# DC4dazzer2.net
KiCad netlist of a schematic drawn in EAGLE
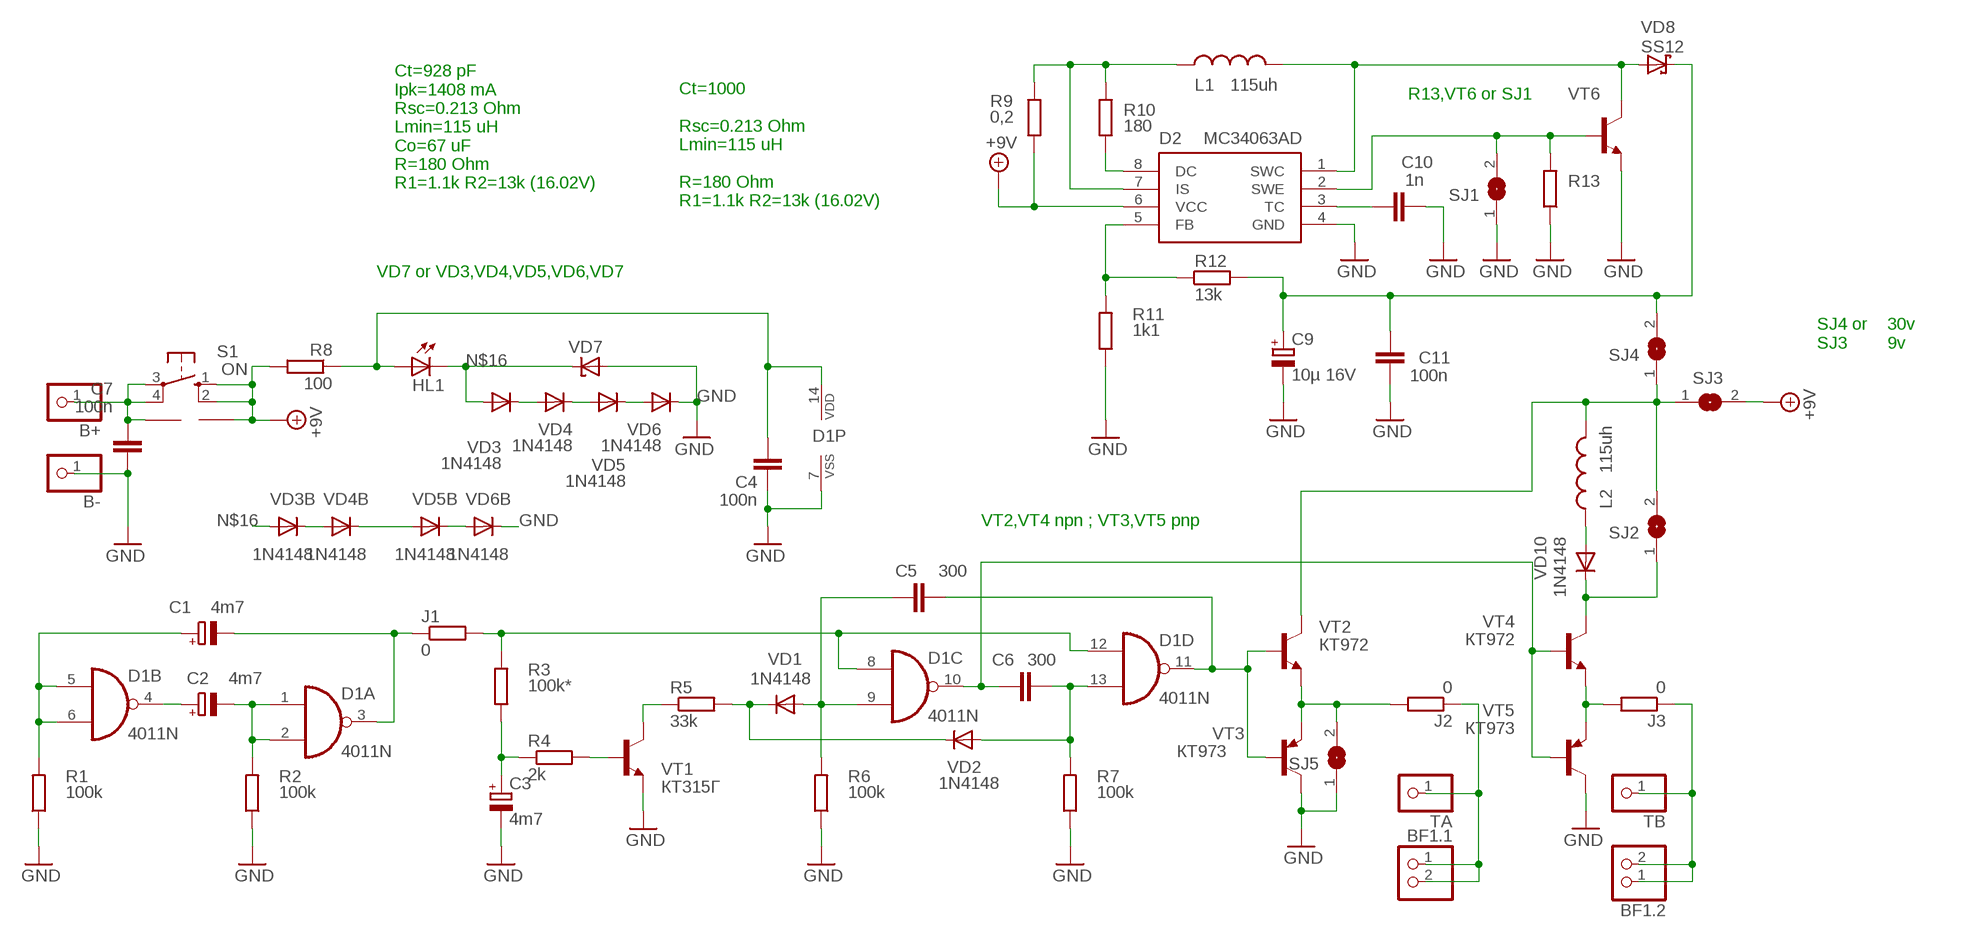
[diagram p0: schematic, sheet 1]

(export (version "E")
  (design (tool "Eeschema 10.0.6"))
  (components
    (comp (ref "B+")
      (value "PINHD-1X1")
      (footprint "eagle-import:1X01")
      (libsource (lib "eagle-import") (part "PINHD-1X1"))
    )
    (comp (ref "B-")
      (value "PINHD-1X1")
      (footprint "eagle-import:1X01")
      (libsource (lib "eagle-import") (part "PINHD-1X1"))
    )
    (comp (ref "BF1.1")
      (value "PINHD-1X2")
      (footprint "eagle-import:1X02")
      (libsource (lib "eagle-import") (part "PINHD-1X2"))
    )
    (comp (ref "BF1.2")
      (value "PINHD-1X2")
      (footprint "eagle-import:1X02")
      (libsource (lib "eagle-import") (part "PINHD-1X2"))
    )
    (comp (ref "C1")
      (value "4m7")
      (footprint "eagle-import:E3,5-8")
      (libsource (lib "eagle-import") (part "CPOL-EUE3.5-8"))
    )
    (comp (ref "C2")
      (value "4m7")
      (footprint "eagle-import:E2,5-7")
      (libsource (lib "eagle-import") (part "CPOL-EUE2.5-7"))
    )
    (comp (ref "C3")
      (value "4m7")
      (footprint "eagle-import:E2,5-7")
      (libsource (lib "eagle-import") (part "CPOL-EUE2.5-7"))
    )
    (comp (ref "C4")
      (value "100n")
      (footprint "eagle-import:C0805")
      (libsource (lib "eagle-import") (part "rcl_C-EUC0805"))
    )
    (comp (ref "C5")
      (value "300")
      (footprint "eagle-import:CAP-PTH-LARGE")
      (libsource (lib "eagle-import") (part "CAPPTH3"))
    )
    (comp (ref "C6")
      (value "300")
      (footprint "eagle-import:CAP-PTH-LARGE")
      (libsource (lib "eagle-import") (part "CAPPTH3"))
    )
    (comp (ref "C7")
      (value "100n")
      (footprint "eagle-import:C025-024X044")
      (libsource (lib "eagle-import") (part "C-EU025-024X044"))
    )
    (comp (ref "C9")
      (value "10µ 16V")
      (footprint "eagle-import:RCL_E3,5-8")
      (libsource (lib "eagle-import") (part "RCL_CPOL-EUE3.5-8"))
    )
    (comp (ref "C10")
      (value "1n")
      (footprint "eagle-import:C025-025X050")
      (libsource (lib "eagle-import") (part "rcl_C-EU025-025X050"))
    )
    (comp (ref "C11")
      (value "100n")
      (footprint "eagle-import:C0805")
      (libsource (lib "eagle-import") (part "rcl_C-EUC0805"))
    )
    (comp (ref "D1")
      (value "4011N")
      (footprint "eagle-import:DIL14")
      (libsource (lib "eagle-import") (part "4011N"))
    )
    (comp (ref "D2")
      (value "MC34063AD")
      (footprint "eagle-import:SOIC8")
      (libsource (lib "eagle-import") (part "MC34063AD"))
    )
    (comp (ref "HL1")
      (value "LED5MM")
      (footprint "eagle-import:LED5MM")
      (libsource (lib "eagle-import") (part "LED5MM"))
    )
    (comp (ref "J1")
      (value "0")
      (footprint "eagle-import:R1206W")
      (libsource (lib "eagle-import") (part "R-EU_R1206W"))
    )
    (comp (ref "J2")
      (value "0")
      (footprint "eagle-import:R1206W")
      (libsource (lib "eagle-import") (part "R-EU_R1206W"))
    )
    (comp (ref "J3")
      (value "0")
      (footprint "eagle-import:R1206W")
      (libsource (lib "eagle-import") (part "R-EU_R1206W"))
    )
    (comp (ref "L1")
      (value "115uh")
      (footprint "eagle-import:0207_10")
      (libsource (lib "eagle-import") (part "L-US0207/10"))
    )
    (comp (ref "L2")
      (value "115uh")
      (footprint "eagle-import:0204_5")
      (libsource (lib "eagle-import") (part "L-US0204/5"))
    )
    (comp (ref "R1")
      (value "100k")
      (footprint "eagle-import:R0805")
      (libsource (lib "eagle-import") (part "R-EU_R0805"))
    )
    (comp (ref "R2")
      (value "100k")
      (footprint "eagle-import:R0805")
      (libsource (lib "eagle-import") (part "R-EU_R0805"))
    )
    (comp (ref "R3")
      (value "100k*")
      (footprint "eagle-import:0204_7")
      (libsource (lib "eagle-import") (part "R-EU_0204/7"))
    )
    (comp (ref "R4")
      (value "2k")
      (footprint "eagle-import:R0805")
      (libsource (lib "eagle-import") (part "R-EU_R0805"))
    )
    (comp (ref "R5")
      (value "33k")
      (footprint "eagle-import:R1206W")
      (libsource (lib "eagle-import") (part "R-EU_R1206W"))
    )
    (comp (ref "R6")
      (value "100k")
      (footprint "eagle-import:R1206W")
      (libsource (lib "eagle-import") (part "R-EU_R1206W"))
    )
    (comp (ref "R7")
      (value "100k")
      (footprint "eagle-import:M0805")
      (libsource (lib "eagle-import") (part "R-EU_M0805"))
    )
    (comp (ref "R8")
      (value "100")
      (footprint "eagle-import:0204_5")
      (libsource (lib "eagle-import") (part "R-EU_0204/5"))
    )
    (comp (ref "R9")
      (value "0,2")
      (footprint "eagle-import:0204_7")
      (libsource (lib "eagle-import") (part "R-EU_0204/7"))
    )
    (comp (ref "R10")
      (value "180")
      (footprint "eagle-import:0204_7")
      (libsource (lib "eagle-import") (part "R-EU_0204/7"))
    )
    (comp (ref "R11")
      (value "1k1")
      (footprint "eagle-import:M0805")
      (libsource (lib "eagle-import") (part "R-EU_M0805"))
    )
    (comp (ref "R12")
      (value "13k")
      (footprint "eagle-import:M0805")
      (libsource (lib "eagle-import") (part "R-EU_M0805"))
    )
    (comp (ref "R13")
      (value "R-EU_0204/7")
      (footprint "eagle-import:0204_7")
      (libsource (lib "eagle-import") (part "R-EU_0204/7"))
    )
    (comp (ref "S1")
      (value "ON")
      (footprint "eagle-import:B3F-10XX")
      (fields (field (name "MPN") "B3F-1000"))
      (libsource (lib "eagle-import") (part "10-XX"))
    )
    (comp (ref "SJ1") (value "SJ") (footprint "eagle-import:SJ") (libsource (lib "eagle-import") (part "SJ")))
    (comp (ref "SJ2") (value "SJ") (footprint "eagle-import:SJ") (libsource (lib "eagle-import") (part "SJ")))
    (comp (ref "SJ3") (value "SJ") (footprint "eagle-import:SJ") (libsource (lib "eagle-import") (part "SJ")))
    (comp (ref "SJ4") (value "SJ") (footprint "eagle-import:SJ") (libsource (lib "eagle-import") (part "SJ")))
    (comp (ref "SJ5") (value "SJ") (footprint "eagle-import:SJ") (libsource (lib "eagle-import") (part "SJ")))
    (comp (ref "TA")
      (value "PINHD-1X1")
      (footprint "eagle-import:1X01")
      (libsource (lib "eagle-import") (part "PINHD-1X1"))
    )
    (comp (ref "TB")
      (value "PINHD-1X1")
      (footprint "eagle-import:1X01")
      (libsource (lib "eagle-import") (part "PINHD-1X1"))
    )
    (comp (ref "U$2")
      (value "PROGRAMMER_5.08")
      (footprint "eagle-import:PROGRAMMER_KEY")
      (libsource (lib "eagle-import") (part "PROGRAMMER_5.08"))
    )
    (comp (ref "VD1")
      (value "1N4148")
      (footprint "eagle-import:SOD80C")
      (libsource (lib "eagle-import") (part "DIODE-SOD80C"))
    )
    (comp (ref "VD2")
      (value "1N4148")
      (footprint "eagle-import:SOD80C")
      (libsource (lib "eagle-import") (part "DIODE-SOD80C"))
    )
    (comp (ref "VD3")
      (value "1N4148")
      (footprint "eagle-import:DO35-7")
      (libsource (lib "eagle-import") (part "1N4148DO35-7"))
    )
    (comp (ref "VD3B")
      (value "1N4148")
      (footprint "eagle-import:SOD80C")
      (libsource (lib "eagle-import") (part "DIODE-SOD80C"))
    )
    (comp (ref "VD4")
      (value "1N4148")
      (footprint "eagle-import:DO35-7")
      (libsource (lib "eagle-import") (part "1N4148DO35-7"))
    )
    (comp (ref "VD4B")
      (value "1N4148")
      (footprint "eagle-import:SOD80C")
      (libsource (lib "eagle-import") (part "DIODE-SOD80C"))
    )
    (comp (ref "VD5")
      (value "1N4148")
      (footprint "eagle-import:DO35-7")
      (libsource (lib "eagle-import") (part "1N4148DO35-7"))
    )
    (comp (ref "VD5B")
      (value "1N4148")
      (footprint "eagle-import:SOD80C")
      (libsource (lib "eagle-import") (part "DIODE-SOD80C"))
    )
    (comp (ref "VD6")
      (value "1N4148")
      (footprint "eagle-import:DO35-7")
      (libsource (lib "eagle-import") (part "1N4148DO35-7"))
    )
    (comp (ref "VD6B")
      (value "1N4148")
      (footprint "eagle-import:SOD80C")
      (libsource (lib "eagle-import") (part "DIODE-SOD80C"))
    )
    (comp (ref "VD7")
      (value "ZENER-DIODEZD-7.5")
      (footprint "eagle-import:ZDIO-7.5")
      (libsource (lib "eagle-import") (part "ZENER-DIODEZD-7.5"))
    )
    (comp (ref "VD8")
      (value "SS12")
      (footprint "eagle-import:SMB")
      (libsource (lib "eagle-import") (part "SCHOTTKY-DIODESMD"))
    )
    (comp (ref "VD10")
      (value "1N4148")
      (footprint "eagle-import:SOD80C")
      (libsource (lib "eagle-import") (part "DIODE-SOD80C"))
    )
    (comp (ref "VT1")
      (value "КТ315Г")
      (footprint "eagle-import:TO92-ECB")
      (libsource (lib "eagle-import") (part "-NPN-TO92-ECBBC167"))
    )
    (comp (ref "VT2")
      (value "КТ972")
      (footprint "eagle-import:TO92-ECB")
      (libsource (lib "eagle-import") (part "-NPN-TO92-ECBBC167"))
    )
    (comp (ref "VT3")
      (value "КТ973")
      (footprint "eagle-import:TO92-BCE")
      (libsource (lib "eagle-import") (part "-PNP-TO92-BCEBC369"))
    )
    (comp (ref "VT4")
      (value "КТ972")
      (footprint "eagle-import:TO92-ECB")
      (libsource (lib "eagle-import") (part "-NPN-TO92-ECBBC167"))
    )
    (comp (ref "VT5")
      (value "КТ973")
      (footprint "eagle-import:TO92-BCE")
      (libsource (lib "eagle-import") (part "-PNP-TO92-BCEBC369"))
    )
    (comp (ref "VT6")
      (value "BC167-NPN-TO92-ECB")
      (footprint "eagle-import:TO92-ECB")
      (libsource (lib "eagle-import") (part "-NPN-TO92-ECBBC167"))
    )
  )
  (nets
    (net (code "1") (name "+9V") (class "Default")
      (node (ref "D2") (pin "6") (pinfunction "VCC_6") (pintype "passive"))
      (node (ref "R8") (pin "2") (pinfunction "2_2") (pintype "passive"))
      (node (ref "R9") (pin "1") (pinfunction "1_1") (pintype "passive"))
      (node (ref "S1") (pin "1") (pinfunction "S_1") (pintype "passive"))
      (node (ref "S1") (pin "2") (pinfunction "S1_2") (pintype "passive"))
      (node (ref "SJ3") (pin "2") (pinfunction "2_2") (pintype "passive"))
      (node (ref "U$2") (pin "P$2") (pinfunction "P$2_P$2") (pintype "bidirectional"))
    )
    (net (code "2") (name "/N$16") (class "Default")
      (node (ref "HL1") (pin "K") (pinfunction "C_K") (pintype "passive"))
      (node (ref "VD3") (pin "A") (pinfunction "A_A") (pintype "passive"))
      (node (ref "VD3B") (pin "A") (pinfunction "A_A") (pintype "passive"))
      (node (ref "VD7") (pin "C") (pinfunction "C_C") (pintype "passive"))
    )
    (net (code "3") (name "/N$21") (class "Default")
      (node (ref "VD3") (pin "C") (pinfunction "C_C") (pintype "passive"))
      (node (ref "VD3B") (pin "C") (pinfunction "C_C") (pintype "passive"))
      (node (ref "VD4") (pin "A") (pinfunction "A_A") (pintype "passive"))
      (node (ref "VD4B") (pin "A") (pinfunction "A_A") (pintype "passive"))
    )
    (net (code "4") (name "/N$22") (class "Default")
      (node (ref "VD4") (pin "C") (pinfunction "C_C") (pintype "passive"))
      (node (ref "VD4B") (pin "C") (pinfunction "C_C") (pintype "passive"))
      (node (ref "VD5") (pin "A") (pinfunction "A_A") (pintype "passive"))
      (node (ref "VD5B") (pin "A") (pinfunction "A_A") (pintype "passive"))
    )
    (net (code "5") (name "/N$23") (class "Default")
      (node (ref "VD5") (pin "C") (pinfunction "C_C") (pintype "passive"))
      (node (ref "VD5B") (pin "C") (pinfunction "C_C") (pintype "passive"))
      (node (ref "VD6") (pin "A") (pinfunction "A_A") (pintype "passive"))
      (node (ref "VD6B") (pin "A") (pinfunction "A_A") (pintype "passive"))
    )
    (net (code "6") (name "GND") (class "Default")
      (node (ref "B-") (pin "1") (pinfunction "1_1") (pintype "passive"))
      (node (ref "C10") (pin "2") (pinfunction "2_2") (pintype "passive"))
      (node (ref "C11") (pin "1") (pinfunction "1_1") (pintype "passive"))
      (node (ref "C3") (pin "-") (pinfunction "-_-") (pintype "passive"))
      (node (ref "C4") (pin "2") (pinfunction "2_2") (pintype "passive"))
      (node (ref "C7") (pin "2") (pinfunction "2_2") (pintype "passive"))
      (node (ref "C9") (pin "-") (pinfunction "-_-") (pintype "passive"))
      (node (ref "D1") (pin "7") (pinfunction "VSS_7") (pintype "power_in"))
      (node (ref "D2") (pin "4") (pinfunction "GND_4") (pintype "passive"))
      (node (ref "R1") (pin "1") (pinfunction "1_1") (pintype "passive"))
      (node (ref "R11") (pin "1") (pinfunction "1_1") (pintype "passive"))
      (node (ref "R13") (pin "1") (pinfunction "1_1") (pintype "passive"))
      (node (ref "R2") (pin "1") (pinfunction "1_1") (pintype "passive"))
      (node (ref "R6") (pin "1") (pinfunction "1_1") (pintype "passive"))
      (node (ref "R7") (pin "1") (pinfunction "1_1") (pintype "passive"))
      (node (ref "SJ1") (pin "1") (pinfunction "1_1") (pintype "passive"))
      (node (ref "SJ5") (pin "1") (pinfunction "1_1") (pintype "passive"))
      (node (ref "VD6") (pin "C") (pinfunction "C_C") (pintype "passive"))
      (node (ref "VD6B") (pin "C") (pinfunction "C_C") (pintype "passive"))
      (node (ref "VD7") (pin "A") (pinfunction "A_A") (pintype "passive"))
      (node (ref "VT1") (pin "E") (pinfunction "E_E") (pintype "passive"))
      (node (ref "VT3") (pin "C") (pinfunction "C_C") (pintype "passive"))
      (node (ref "VT5") (pin "C") (pinfunction "C_C") (pintype "passive"))
      (node (ref "VT6") (pin "E") (pinfunction "E_E") (pintype "passive"))
    )
    (net (code "7") (name "Net-(BF1.1-Pad1)") (class "Default")
      (node (ref "BF1.1") (pin "1") (pinfunction "1_1") (pintype "passive"))
      (node (ref "BF1.1") (pin "2") (pinfunction "2_2") (pintype "passive"))
      (node (ref "J2") (pin "1") (pinfunction "1_1") (pintype "passive"))
      (node (ref "TA") (pin "1") (pinfunction "1_1") (pintype "passive"))
    )
    (net (code "8") (name "Net-(BF1.2-Pad1)") (class "Default")
      (node (ref "BF1.2") (pin "1") (pinfunction "1_1") (pintype "passive"))
      (node (ref "BF1.2") (pin "2") (pinfunction "2_2") (pintype "passive"))
      (node (ref "J3") (pin "1") (pinfunction "1_1") (pintype "passive"))
      (node (ref "TB") (pin "1") (pinfunction "1_1") (pintype "passive"))
    )
    (net (code "9") (name "Net-(C3-Pad+)") (class "Default")
      (node (ref "C3") (pin "+") (pinfunction "+_+") (pintype "passive"))
      (node (ref "R3") (pin "1") (pinfunction "1_1") (pintype "passive"))
      (node (ref "R4") (pin "1") (pinfunction "1_1") (pintype "passive"))
    )
    (net (code "10") (name "Net-(C11-Pad2)") (class "Default")
      (node (ref "C11") (pin "2") (pinfunction "2_2") (pintype "passive"))
      (node (ref "C9") (pin "+") (pinfunction "+_+") (pintype "passive"))
      (node (ref "R12") (pin "2") (pinfunction "2_2") (pintype "passive"))
      (node (ref "SJ4") (pin "2") (pinfunction "2_2") (pintype "passive"))
      (node (ref "VD8") (pin "C") (pinfunction "C_C") (pintype "passive"))
    )
    (net (code "11") (name "Net-(D1A-I0)") (class "Default")
      (node (ref "C2") (pin "-") (pinfunction "-_-") (pintype "passive"))
      (node (ref "D1") (pin "1") (pinfunction "I0_1") (pintype "input"))
      (node (ref "D1") (pin "2") (pinfunction "I1_2") (pintype "input"))
      (node (ref "R2") (pin "2") (pinfunction "2_2") (pintype "passive"))
    )
    (net (code "12") (name "Net-(D1A-O)") (class "Default")
      (node (ref "C1") (pin "-") (pinfunction "-_-") (pintype "passive"))
      (node (ref "D1") (pin "3") (pinfunction "O_3") (pintype "output"))
      (node (ref "J1") (pin "1") (pinfunction "1_1") (pintype "passive"))
    )
    (net (code "13") (name "Net-(D1B-I0)") (class "Default")
      (node (ref "C1") (pin "+") (pinfunction "+_+") (pintype "passive"))
      (node (ref "D1") (pin "5") (pinfunction "I0_5") (pintype "input"))
      (node (ref "D1") (pin "6") (pinfunction "I1_6") (pintype "input"))
      (node (ref "R1") (pin "2") (pinfunction "2_2") (pintype "passive"))
    )
    (net (code "14") (name "Net-(D1B-O)") (class "Default")
      (node (ref "C2") (pin "+") (pinfunction "+_+") (pintype "passive"))
      (node (ref "D1") (pin "4") (pinfunction "O_4") (pintype "output"))
    )
    (net (code "15") (name "Net-(D1C-I0)") (class "Default")
      (node (ref "D1") (pin "12") (pinfunction "I0_12") (pintype "input"))
      (node (ref "D1") (pin "8") (pinfunction "I0_8") (pintype "input"))
      (node (ref "J1") (pin "2") (pinfunction "2_2") (pintype "passive"))
      (node (ref "R3") (pin "2") (pinfunction "2_2") (pintype "passive"))
    )
    (net (code "16") (name "Net-(D1C-I1)") (class "Default")
      (node (ref "C5") (pin "1") (pinfunction "1_1") (pintype "passive"))
      (node (ref "D1") (pin "9") (pinfunction "I1_9") (pintype "input"))
      (node (ref "R6") (pin "2") (pinfunction "2_2") (pintype "passive"))
      (node (ref "VD1") (pin "A") (pinfunction "A_A") (pintype "passive"))
    )
    (net (code "17") (name "Net-(D1C-O)") (class "Default")
      (node (ref "C6") (pin "1") (pinfunction "1_1") (pintype "passive"))
      (node (ref "D1") (pin "10") (pinfunction "O_10") (pintype "output"))
      (node (ref "VT4") (pin "B") (pinfunction "B_B") (pintype "passive"))
      (node (ref "VT5") (pin "B") (pinfunction "B_B") (pintype "passive"))
    )
    (net (code "18") (name "Net-(D1D-I1)") (class "Default")
      (node (ref "C6") (pin "2") (pinfunction "2_2") (pintype "passive"))
      (node (ref "D1") (pin "13") (pinfunction "I1_13") (pintype "input"))
      (node (ref "R7") (pin "2") (pinfunction "2_2") (pintype "passive"))
      (node (ref "VD2") (pin "A") (pinfunction "A_A") (pintype "passive"))
    )
    (net (code "19") (name "Net-(D1D-O)") (class "Default")
      (node (ref "C5") (pin "2") (pinfunction "2_2") (pintype "passive"))
      (node (ref "D1") (pin "11") (pinfunction "O_11") (pintype "output"))
      (node (ref "VT2") (pin "B") (pinfunction "B_B") (pintype "passive"))
      (node (ref "VT3") (pin "B") (pinfunction "B_B") (pintype "passive"))
    )
    (net (code "20") (name "Net-(D1E-VDD)") (class "Default")
      (node (ref "C4") (pin "1") (pinfunction "1_1") (pintype "passive"))
      (node (ref "D1") (pin "14") (pinfunction "VDD_14") (pintype "power_in"))
      (node (ref "HL1") (pin "A") (pinfunction "A_A") (pintype "passive"))
      (node (ref "R8") (pin "1") (pinfunction "1_1") (pintype "passive"))
    )
    (net (code "21") (name "Net-(D2-DC)") (class "Default")
      (node (ref "D2") (pin "8") (pinfunction "DC_8") (pintype "passive"))
      (node (ref "R10") (pin "1") (pinfunction "1_1") (pintype "passive"))
    )
    (net (code "22") (name "Net-(D2-FB)") (class "Default")
      (node (ref "D2") (pin "5") (pinfunction "FB_5") (pintype "passive"))
      (node (ref "R11") (pin "2") (pinfunction "2_2") (pintype "passive"))
      (node (ref "R12") (pin "1") (pinfunction "1_1") (pintype "passive"))
    )
    (net (code "23") (name "Net-(D2-IS)") (class "Default")
      (node (ref "D2") (pin "7") (pinfunction "IS_7") (pintype "passive"))
      (node (ref "L1") (pin "1") (pinfunction "1_1") (pintype "passive"))
      (node (ref "R10") (pin "2") (pinfunction "2_2") (pintype "passive"))
      (node (ref "R9") (pin "2") (pinfunction "2_2") (pintype "passive"))
    )
    (net (code "24") (name "Net-(D2-SWC)") (class "Default")
      (node (ref "D2") (pin "1") (pinfunction "SWC_1") (pintype "passive"))
      (node (ref "L1") (pin "2") (pinfunction "2_2") (pintype "passive"))
      (node (ref "VD8") (pin "A") (pinfunction "A_A") (pintype "passive"))
      (node (ref "VT6") (pin "C") (pinfunction "C_C") (pintype "passive"))
    )
    (net (code "25") (name "Net-(D2-SWE)") (class "Default")
      (node (ref "D2") (pin "2") (pinfunction "SWE_2") (pintype "passive"))
      (node (ref "R13") (pin "2") (pinfunction "2_2") (pintype "passive"))
      (node (ref "SJ1") (pin "2") (pinfunction "2_2") (pintype "passive"))
      (node (ref "VT6") (pin "B") (pinfunction "B_B") (pintype "passive"))
    )
    (net (code "26") (name "Net-(D2-TC)") (class "Default")
      (node (ref "C10") (pin "1") (pinfunction "1_1") (pintype "passive"))
      (node (ref "D2") (pin "3") (pinfunction "TC_3") (pintype "passive"))
    )
    (net (code "27") (name "Net-(J2-Pad2)") (class "Default")
      (node (ref "J2") (pin "2") (pinfunction "2_2") (pintype "passive"))
      (node (ref "SJ5") (pin "2") (pinfunction "2_2") (pintype "passive"))
      (node (ref "VT2") (pin "E") (pinfunction "E_E") (pintype "passive"))
      (node (ref "VT3") (pin "E") (pinfunction "E_E") (pintype "passive"))
    )
    (net (code "28") (name "Net-(J3-Pad2)") (class "Default")
      (node (ref "J3") (pin "2") (pinfunction "2_2") (pintype "passive"))
      (node (ref "VT4") (pin "E") (pinfunction "E_E") (pintype "passive"))
      (node (ref "VT5") (pin "E") (pinfunction "E_E") (pintype "passive"))
    )
    (net (code "29") (name "Net-(L2-Pad1)") (class "Default")
      (node (ref "L2") (pin "1") (pinfunction "1_1") (pintype "passive"))
      (node (ref "VD10") (pin "A") (pinfunction "A_A") (pintype "passive"))
    )
    (net (code "30") (name "Net-(L2-Pad2)") (class "Default")
      (node (ref "L2") (pin "2") (pinfunction "2_2") (pintype "passive"))
      (node (ref "SJ2") (pin "2") (pinfunction "2_2") (pintype "passive"))
      (node (ref "SJ3") (pin "1") (pinfunction "1_1") (pintype "passive"))
      (node (ref "SJ4") (pin "1") (pinfunction "1_1") (pintype "passive"))
      (node (ref "VT2") (pin "C") (pinfunction "C_C") (pintype "passive"))
    )
    (net (code "31") (name "Net-(R4-Pad2)") (class "Default")
      (node (ref "R4") (pin "2") (pinfunction "2_2") (pintype "passive"))
      (node (ref "VT1") (pin "B") (pinfunction "B_B") (pintype "passive"))
    )
    (net (code "32") (name "Net-(R5-Pad1)") (class "Default")
      (node (ref "R5") (pin "1") (pinfunction "1_1") (pintype "passive"))
      (node (ref "VT1") (pin "C") (pinfunction "C_C") (pintype "passive"))
    )
    (net (code "33") (name "Net-(R5-Pad2)") (class "Default")
      (node (ref "R5") (pin "2") (pinfunction "2_2") (pintype "passive"))
      (node (ref "VD1") (pin "C") (pinfunction "C_C") (pintype "passive"))
      (node (ref "VD2") (pin "C") (pinfunction "C_C") (pintype "passive"))
    )
    (net (code "34") (name "Net-(S1-P)") (class "Default")
      (node (ref "B+") (pin "1") (pinfunction "1_1") (pintype "passive"))
      (node (ref "C7") (pin "1") (pinfunction "1_1") (pintype "passive"))
      (node (ref "S1") (pin "3") (pinfunction "P_3") (pintype "passive"))
      (node (ref "S1") (pin "4") (pinfunction "P1_4") (pintype "passive"))
      (node (ref "U$2") (pin "P$1") (pinfunction "P$1_P$1") (pintype "bidirectional"))
    )
    (net (code "35") (name "Net-(SJ2-Pad1)") (class "Default")
      (node (ref "SJ2") (pin "1") (pinfunction "1_1") (pintype "passive"))
      (node (ref "VD10") (pin "C") (pinfunction "C_C") (pintype "passive"))
      (node (ref "VT4") (pin "C") (pinfunction "C_C") (pintype "passive"))
    )
  )
)
